# Hand_Module.net
KiCad netlist of a schematic drawn in EAGLE
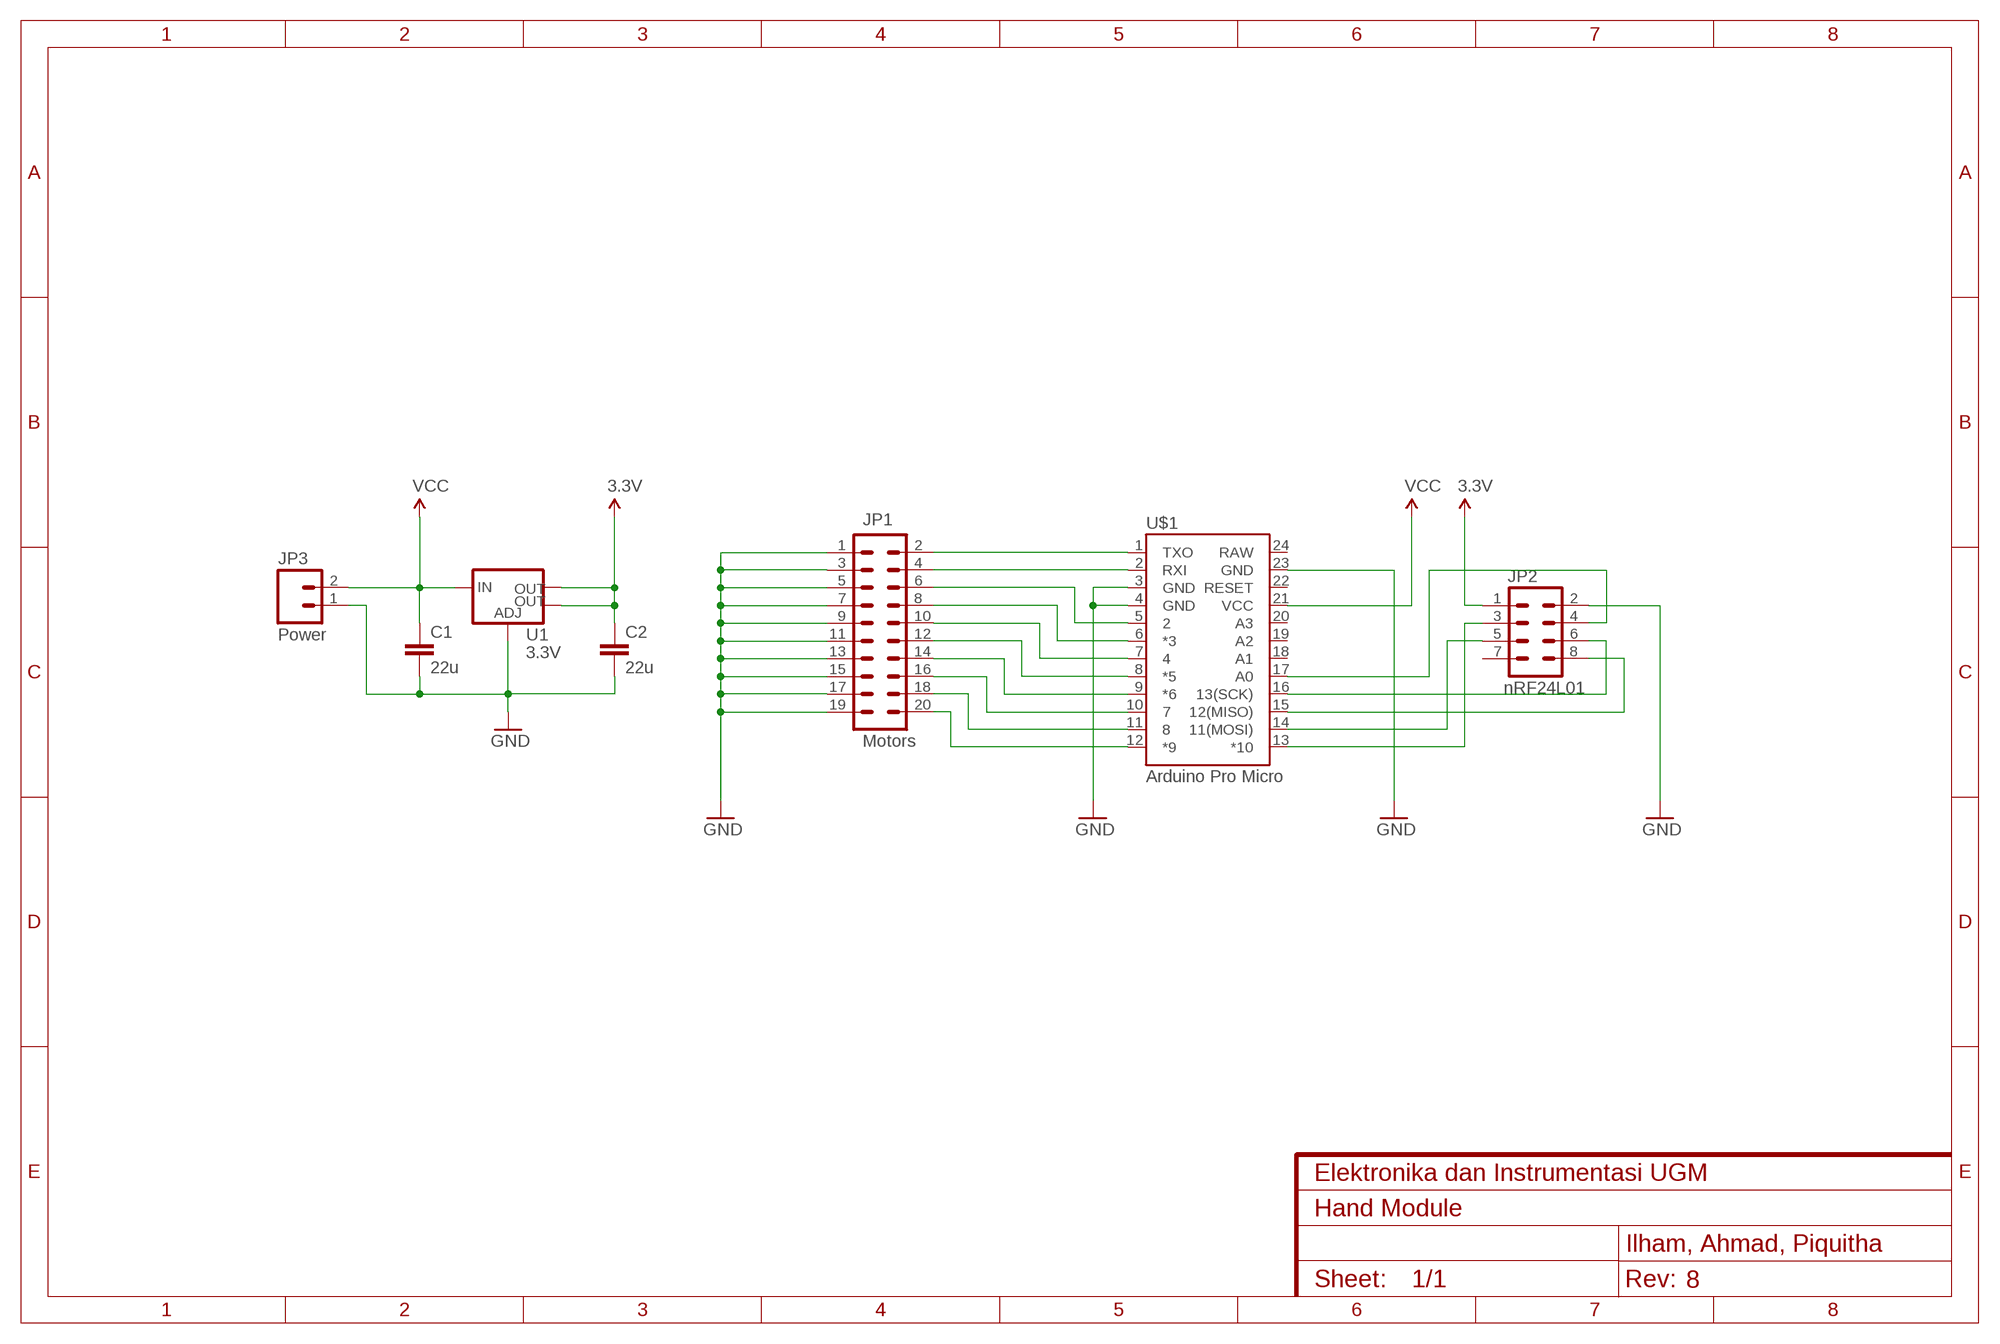
[diagram p0: schematic, sheet 1]

(export (version "E")
  (design (tool "Eeschema 10.0.6"))
  (components
    (comp (ref "C1")
      (value "22u")
      (footprint "eagle-import:0805")
      (libsource (lib "eagle-import") (part "CAP0805"))
    )
    (comp (ref "C2")
      (value "22u")
      (footprint "eagle-import:0805")
      (libsource (lib "eagle-import") (part "CAP0805"))
    )
    (comp (ref "JP1")
      (value "Motors")
      (footprint "eagle-import:2X10")
      (libsource (lib "eagle-import") (part "M10X2"))
    )
    (comp (ref "JP2")
      (value "nRF24L01")
      (footprint "eagle-import:2X4")
      (libsource (lib "eagle-import") (part "M04X2"))
    )
    (comp (ref "JP3")
      (value "Power")
      (footprint "eagle-import:1X02")
      (libsource (lib "eagle-import") (part "M02PTH"))
    )
    (comp (ref "U$1")
      (value "Arduino Pro Micro")
      (footprint "eagle-import:ARDUINO_PRO_MICRO")
      (libsource (lib "eagle-import") (part "ARDUINO_PRO_MICRO"))
    )
    (comp (ref "U1")
      (value "3.3V")
      (footprint "eagle-import:SOT223")
      (libsource (lib "eagle-import") (part "V_REG_LM1117SOT223"))
    )
  )
  (nets
    (net (code "1") (name "3.3V") (class "Default")
      (node (ref "C2") (pin "1") (pinfunction "1_1") (pintype "passive"))
      (node (ref "JP2") (pin "1") (pinfunction "1_1") (pintype "passive"))
      (node (ref "U1") (pin "2") (pinfunction "OUT_2") (pintype "output"))
      (node (ref "U1") (pin "4") (pinfunction "OUT_4") (pintype "output"))
    )
    (net (code "2") (name "GND") (class "Default")
      (node (ref "C1") (pin "2") (pinfunction "2_2") (pintype "passive"))
      (node (ref "C2") (pin "2") (pinfunction "2_2") (pintype "passive"))
      (node (ref "JP1") (pin "1") (pinfunction "1_1") (pintype "passive"))
      (node (ref "JP1") (pin "11") (pinfunction "11_11") (pintype "passive"))
      (node (ref "JP1") (pin "13") (pinfunction "13_13") (pintype "passive"))
      (node (ref "JP1") (pin "15") (pinfunction "15_15") (pintype "passive"))
      (node (ref "JP1") (pin "17") (pinfunction "17_17") (pintype "passive"))
      (node (ref "JP1") (pin "19") (pinfunction "19_19") (pintype "passive"))
      (node (ref "JP1") (pin "3") (pinfunction "3_3") (pintype "passive"))
      (node (ref "JP1") (pin "5") (pinfunction "5_5") (pintype "passive"))
      (node (ref "JP1") (pin "7") (pinfunction "7_7") (pintype "passive"))
      (node (ref "JP1") (pin "9") (pinfunction "9_9") (pintype "passive"))
      (node (ref "JP2") (pin "2") (pinfunction "2_2") (pintype "passive"))
      (node (ref "JP3") (pin "1") (pinfunction "1_1") (pintype "passive"))
      (node (ref "U$1") (pin "23") (pinfunction "GND_23") (pintype "bidirectional"))
      (node (ref "U$1") (pin "3") (pinfunction "GND_3") (pintype "bidirectional"))
      (node (ref "U$1") (pin "4") (pinfunction "GND_4") (pintype "bidirectional"))
      (node (ref "U1") (pin "1") (pinfunction "ADJ_1") (pintype "input"))
    )
    (net (code "3") (name "Net-(U$1-*3)") (class "Default")
      (node (ref "JP1") (pin "8") (pinfunction "8_8") (pintype "passive"))
      (node (ref "U$1") (pin "6") (pinfunction "*3_6") (pintype "bidirectional"))
    )
    (net (code "4") (name "Net-(U$1-*5)") (class "Default")
      (node (ref "JP1") (pin "12") (pinfunction "12_12") (pintype "passive"))
      (node (ref "U$1") (pin "8") (pinfunction "*5_8") (pintype "bidirectional"))
    )
    (net (code "5") (name "Net-(U$1-*6)") (class "Default")
      (node (ref "JP1") (pin "14") (pinfunction "14_14") (pintype "passive"))
      (node (ref "U$1") (pin "9") (pinfunction "*6_9") (pintype "bidirectional"))
    )
    (net (code "6") (name "Net-(U$1-*9)") (class "Default")
      (node (ref "JP1") (pin "20") (pinfunction "20_20") (pintype "passive"))
      (node (ref "U$1") (pin "12") (pinfunction "*9_12") (pintype "bidirectional"))
    )
    (net (code "7") (name "Net-(U$1-*10)") (class "Default")
      (node (ref "JP2") (pin "3") (pinfunction "3_3") (pintype "passive"))
      (node (ref "U$1") (pin "13") (pinfunction "*10_13") (pintype "bidirectional"))
    )
    (net (code "8") (name "Net-(U$1-2)") (class "Default")
      (node (ref "JP1") (pin "6") (pinfunction "6_6") (pintype "passive"))
      (node (ref "U$1") (pin "5") (pinfunction "2_5") (pintype "bidirectional"))
    )
    (net (code "9") (name "Net-(U$1-4)") (class "Default")
      (node (ref "JP1") (pin "10") (pinfunction "10_10") (pintype "passive"))
      (node (ref "U$1") (pin "7") (pinfunction "4_7") (pintype "bidirectional"))
    )
    (net (code "10") (name "Net-(U$1-7)") (class "Default")
      (node (ref "JP1") (pin "16") (pinfunction "16_16") (pintype "passive"))
      (node (ref "U$1") (pin "10") (pinfunction "7_10") (pintype "bidirectional"))
    )
    (net (code "11") (name "Net-(U$1-8)") (class "Default")
      (node (ref "JP1") (pin "18") (pinfunction "18_18") (pintype "passive"))
      (node (ref "U$1") (pin "11") (pinfunction "8_11") (pintype "bidirectional"))
    )
    (net (code "12") (name "Net-(U$1-11(MOSI))") (class "Default")
      (node (ref "JP2") (pin "5") (pinfunction "5_5") (pintype "passive"))
      (node (ref "U$1") (pin "14") (pinfunction "11(MOSI)_14") (pintype "bidirectional"))
    )
    (net (code "13") (name "Net-(U$1-12(MISO))") (class "Default")
      (node (ref "JP2") (pin "8") (pinfunction "8_8") (pintype "passive"))
      (node (ref "U$1") (pin "15") (pinfunction "12(MISO)_15") (pintype "bidirectional"))
    )
    (net (code "14") (name "Net-(U$1-13(SCK))") (class "Default")
      (node (ref "JP2") (pin "6") (pinfunction "6_6") (pintype "passive"))
      (node (ref "U$1") (pin "16") (pinfunction "13(SCK)_16") (pintype "bidirectional"))
    )
    (net (code "15") (name "Net-(U$1-A0)") (class "Default")
      (node (ref "JP2") (pin "4") (pinfunction "4_4") (pintype "passive"))
      (node (ref "U$1") (pin "17") (pinfunction "A0_17") (pintype "bidirectional"))
    )
    (net (code "16") (name "Net-(U$1-RXI)") (class "Default")
      (node (ref "JP1") (pin "4") (pinfunction "4_4") (pintype "passive"))
      (node (ref "U$1") (pin "2") (pinfunction "RXI_2") (pintype "bidirectional"))
    )
    (net (code "17") (name "Net-(U$1-TXO)") (class "Default")
      (node (ref "JP1") (pin "2") (pinfunction "2_2") (pintype "passive"))
      (node (ref "U$1") (pin "1") (pinfunction "TXO_1") (pintype "bidirectional"))
    )
    (net (code "18") (name "VCC") (class "Default")
      (node (ref "C1") (pin "1") (pinfunction "1_1") (pintype "passive"))
      (node (ref "JP3") (pin "2") (pinfunction "2_2") (pintype "passive"))
      (node (ref "U$1") (pin "21") (pinfunction "VCC_21") (pintype "bidirectional"))
      (node (ref "U1") (pin "3") (pinfunction "IN_3") (pintype "input"))
    )
    (net (code "19") (name "unconnected-(JP2-Pad7)") (class "Default")
      (node (ref "JP2") (pin "7") (pinfunction "7_7") (pintype "passive"))
    )
    (net (code "20") (name "unconnected-(U$1-A1-Pad18)") (class "Default")
      (node (ref "U$1") (pin "18") (pinfunction "A1_18") (pintype "bidirectional"))
    )
    (net (code "21") (name "unconnected-(U$1-A2-Pad19)") (class "Default")
      (node (ref "U$1") (pin "19") (pinfunction "A2_19") (pintype "bidirectional"))
    )
    (net (code "22") (name "unconnected-(U$1-A3-Pad20)") (class "Default")
      (node (ref "U$1") (pin "20") (pinfunction "A3_20") (pintype "bidirectional"))
    )
    (net (code "23") (name "unconnected-(U$1-RAW-Pad24)") (class "Default")
      (node (ref "U$1") (pin "24") (pinfunction "RAW_24") (pintype "bidirectional"))
    )
    (net (code "24") (name "unconnected-(U$1-RESET-Pad22)") (class "Default")
      (node (ref "U$1") (pin "22") (pinfunction "RESET_22") (pintype "bidirectional"))
    )
  )
)
